# Sensorboard.net
KiCad netlist of a schematic drawn in EAGLE
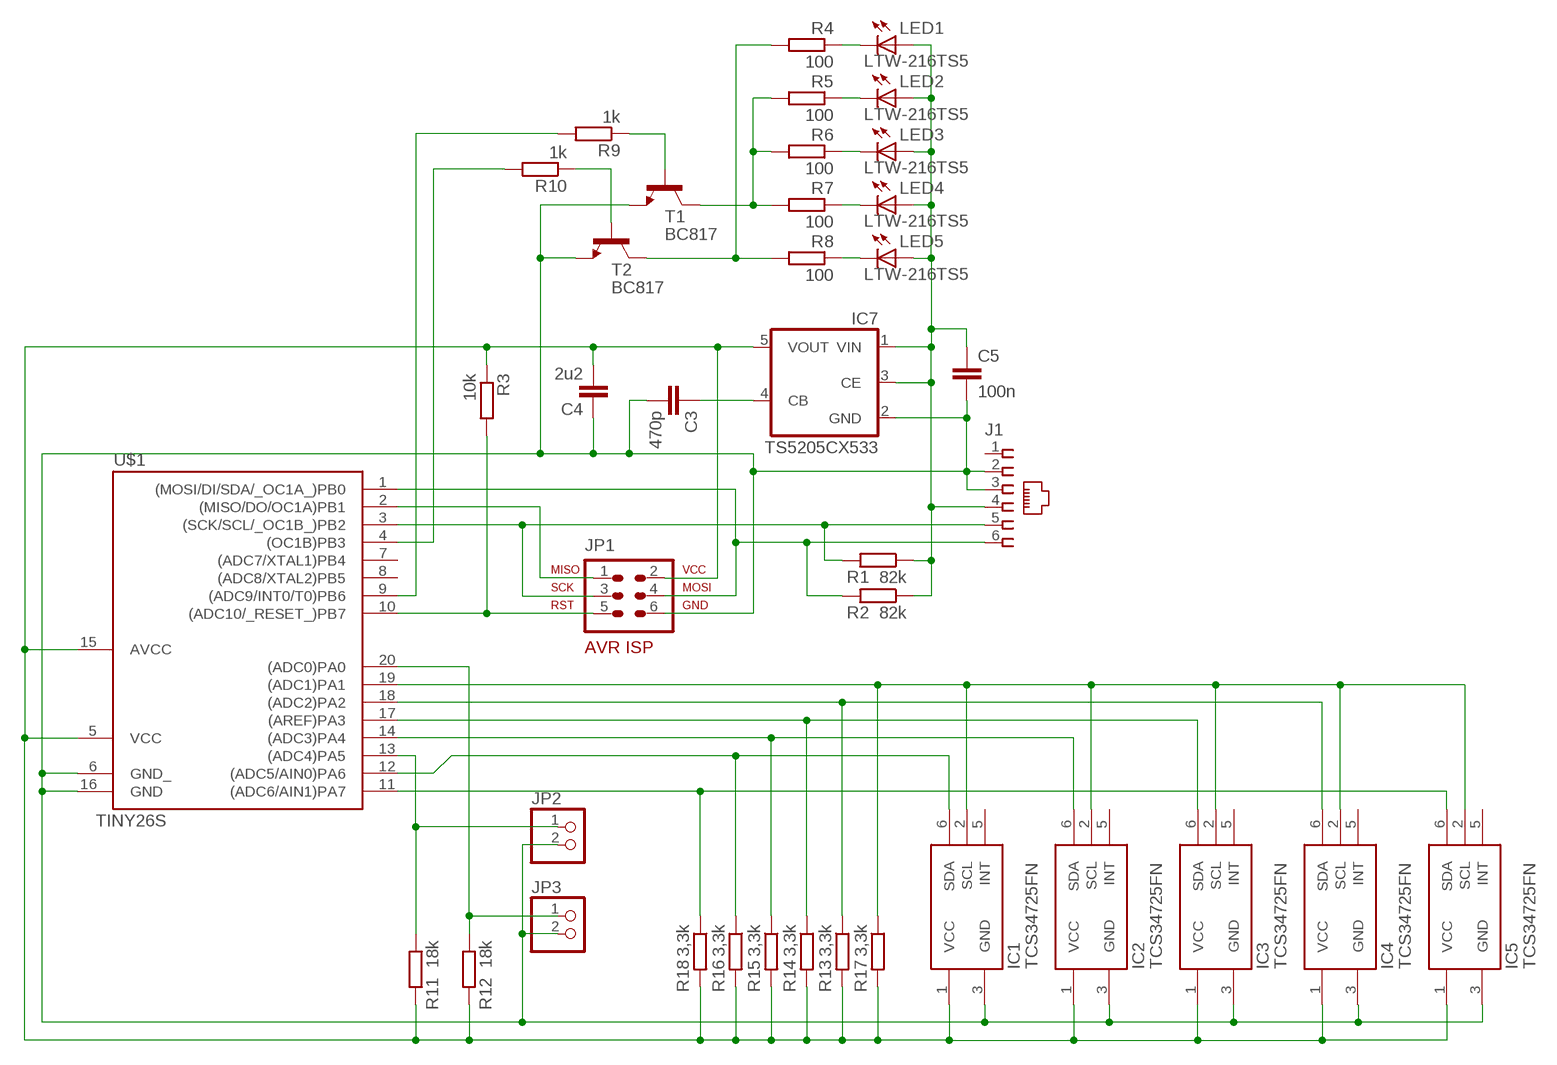
[diagram p0: schematic, sheet 1]

(export (version "E")
  (design (tool "Eeschema 10.0.6"))
  (components
    (comp (ref "C3")
      (value "470p")
      (footprint "eagle-import:C2012")
      (libsource (lib "eagle-import") (part "C-EUC2012"))
    )
    (comp (ref "C4")
      (value "2u2")
      (footprint "eagle-import:C2012")
      (libsource (lib "eagle-import") (part "C-EUC2012"))
    )
    (comp (ref "C5")
      (value "100n")
      (footprint "eagle-import:C2012")
      (libsource (lib "eagle-import") (part "C-EUC2012"))
    )
    (comp (ref "IC1")
      (value "TCS34725FN")
      (footprint "eagle-import:DFN-6")
      (libsource (lib "eagle-import") (part "TCS3472FN"))
    )
    (comp (ref "IC2")
      (value "TCS34725FN")
      (footprint "eagle-import:DFN-6")
      (libsource (lib "eagle-import") (part "TCS3472FN"))
    )
    (comp (ref "IC3")
      (value "TCS34725FN")
      (footprint "eagle-import:DFN-6")
      (libsource (lib "eagle-import") (part "TCS3472FN"))
    )
    (comp (ref "IC4")
      (value "TCS34725FN")
      (footprint "eagle-import:DFN-6")
      (libsource (lib "eagle-import") (part "TCS3472FN"))
    )
    (comp (ref "IC5")
      (value "TCS34725FN")
      (footprint "eagle-import:DFN-6")
      (libsource (lib "eagle-import") (part "TCS3472FN"))
    )
    (comp (ref "IC7")
      (value "TS5205CX533")
      (footprint "eagle-import:SOT25")
      (libsource (lib "eagle-import") (part "TS520533"))
    )
    (comp (ref "J1")
      (value "NXT")
      (footprint "eagle-import:NXT")
      (libsource (lib "eagle-import") (part "NXT"))
    )
    (comp (ref "JP1")
      (value "AVR-ISP-6VERT")
      (footprint "eagle-import:AVR-ISP-6")
      (libsource (lib "eagle-import") (part "AVR-ISP-6VERT"))
    )
    (comp (ref "JP2")
      (value "PINHD-1X2")
      (footprint "eagle-import:1X02")
      (libsource (lib "eagle-import") (part "PINHD-1X2"))
    )
    (comp (ref "JP3")
      (value "PINHD-1X2")
      (footprint "eagle-import:1X02")
      (libsource (lib "eagle-import") (part "PINHD-1X2"))
    )
    (comp (ref "LED1")
      (value "LTW-216TS5")
      (footprint "eagle-import:CHIPLED_1206")
      (libsource (lib "eagle-import") (part "LEDCHIPLED_1206"))
    )
    (comp (ref "LED2")
      (value "LTW-216TS5")
      (footprint "eagle-import:CHIPLED_1206")
      (libsource (lib "eagle-import") (part "LEDCHIPLED_1206"))
    )
    (comp (ref "LED3")
      (value "LTW-216TS5")
      (footprint "eagle-import:CHIPLED_1206")
      (libsource (lib "eagle-import") (part "LEDCHIPLED_1206"))
    )
    (comp (ref "LED4")
      (value "LTW-216TS5")
      (footprint "eagle-import:CHIPLED_1206")
      (libsource (lib "eagle-import") (part "LEDCHIPLED_1206"))
    )
    (comp (ref "LED5")
      (value "LTW-216TS5")
      (footprint "eagle-import:CHIPLED_1206")
      (libsource (lib "eagle-import") (part "LEDCHIPLED_1206"))
    )
    (comp (ref "R1")
      (value "82k")
      (footprint "eagle-import:M0805")
      (libsource (lib "eagle-import") (part "R-EU_M0805"))
    )
    (comp (ref "R2")
      (value "82k")
      (footprint "eagle-import:M0805")
      (libsource (lib "eagle-import") (part "R-EU_M0805"))
    )
    (comp (ref "R3")
      (value "10k")
      (footprint "eagle-import:M0805")
      (libsource (lib "eagle-import") (part "R-EU_M0805"))
    )
    (comp (ref "R4")
      (value "100")
      (footprint "eagle-import:M0805")
      (libsource (lib "eagle-import") (part "R-EU_M0805"))
    )
    (comp (ref "R5")
      (value "100")
      (footprint "eagle-import:M0805")
      (libsource (lib "eagle-import") (part "R-EU_M0805"))
    )
    (comp (ref "R6")
      (value "100")
      (footprint "eagle-import:M0805")
      (libsource (lib "eagle-import") (part "R-EU_M0805"))
    )
    (comp (ref "R7")
      (value "100")
      (footprint "eagle-import:M0805")
      (libsource (lib "eagle-import") (part "R-EU_M0805"))
    )
    (comp (ref "R8")
      (value "100")
      (footprint "eagle-import:M0805")
      (libsource (lib "eagle-import") (part "R-EU_M0805"))
    )
    (comp (ref "R9")
      (value "1k")
      (footprint "eagle-import:M0805")
      (libsource (lib "eagle-import") (part "R-EU_M0805"))
    )
    (comp (ref "R10")
      (value "1k")
      (footprint "eagle-import:M0805")
      (libsource (lib "eagle-import") (part "R-EU_M0805"))
    )
    (comp (ref "R11")
      (value "18k")
      (footprint "eagle-import:M0805")
      (libsource (lib "eagle-import") (part "R-EU_M0805"))
    )
    (comp (ref "R12")
      (value "18k")
      (footprint "eagle-import:M0805")
      (libsource (lib "eagle-import") (part "R-EU_M0805"))
    )
    (comp (ref "R13")
      (value "3,3k")
      (footprint "eagle-import:M0805")
      (libsource (lib "eagle-import") (part "R-EU_M0805"))
    )
    (comp (ref "R14")
      (value "3,3k")
      (footprint "eagle-import:M0805")
      (libsource (lib "eagle-import") (part "R-EU_M0805"))
    )
    (comp (ref "R15")
      (value "3,3k")
      (footprint "eagle-import:M0805")
      (libsource (lib "eagle-import") (part "R-EU_M0805"))
    )
    (comp (ref "R16")
      (value "3,3k")
      (footprint "eagle-import:M0805")
      (libsource (lib "eagle-import") (part "R-EU_M0805"))
    )
    (comp (ref "R17")
      (value "3,3k")
      (footprint "eagle-import:M0805")
      (libsource (lib "eagle-import") (part "R-EU_M0805"))
    )
    (comp (ref "R18")
      (value "3,3k")
      (footprint "eagle-import:M0805")
      (libsource (lib "eagle-import") (part "R-EU_M0805"))
    )
    (comp (ref "T1")
      (value "BC817")
      (footprint "eagle-import:SOT23")
      (libsource (lib "eagle-import") (part "BC846"))
    )
    (comp (ref "T2")
      (value "BC817")
      (footprint "eagle-import:SOT23")
      (libsource (lib "eagle-import") (part "BC846"))
    )
    (comp (ref "U$1")
      (value "TINY26S")
      (footprint "eagle-import:SO20L$")
      (libsource (lib "eagle-import") (part "TINY26S"))
    )
  )
  (nets
    (net (code "1") (name "Net-(IC1-GND)") (class "Default")
      (node (ref "C3") (pin "2") (pinfunction "2_2") (pintype "passive"))
      (node (ref "C4") (pin "1") (pinfunction "1_1") (pintype "passive"))
      (node (ref "C5") (pin "2") (pinfunction "2_2") (pintype "passive"))
      (node (ref "IC1") (pin "3") (pinfunction "GND_3") (pintype "power_in"))
      (node (ref "IC2") (pin "3") (pinfunction "GND_3") (pintype "power_in"))
      (node (ref "IC3") (pin "3") (pinfunction "GND_3") (pintype "power_in"))
      (node (ref "IC4") (pin "3") (pinfunction "GND_3") (pintype "power_in"))
      (node (ref "IC5") (pin "3") (pinfunction "GND_3") (pintype "power_in"))
      (node (ref "IC7") (pin "2") (pinfunction "GND_2") (pintype "passive"))
      (node (ref "J1") (pin "2") (pinfunction "2_2") (pintype "passive"))
      (node (ref "J1") (pin "3") (pinfunction "3_3") (pintype "passive"))
      (node (ref "JP1") (pin "6") (pinfunction "6_6") (pintype "passive"))
      (node (ref "JP2") (pin "2") (pinfunction "2_2") (pintype "passive"))
      (node (ref "JP3") (pin "2") (pinfunction "2_2") (pintype "passive"))
      (node (ref "T1") (pin "2") (pinfunction "E_2") (pintype "passive"))
      (node (ref "T2") (pin "2") (pinfunction "E_2") (pintype "passive"))
      (node (ref "U$1") (pin "16") (pinfunction "GND_16") (pintype "power_in"))
      (node (ref "U$1") (pin "6") (pinfunction "GND__6") (pintype "power_in"))
    )
    (net (code "2") (name "Net-(IC1-SCL)") (class "Default")
      (node (ref "IC1") (pin "2") (pinfunction "SCL_2") (pintype "bidirectional"))
      (node (ref "IC2") (pin "2") (pinfunction "SCL_2") (pintype "bidirectional"))
      (node (ref "IC3") (pin "2") (pinfunction "SCL_2") (pintype "bidirectional"))
      (node (ref "IC4") (pin "2") (pinfunction "SCL_2") (pintype "bidirectional"))
      (node (ref "IC5") (pin "2") (pinfunction "SCL_2") (pintype "bidirectional"))
      (node (ref "R17") (pin "1") (pinfunction "1_1") (pintype "passive"))
      (node (ref "U$1") (pin "19") (pinfunction "(ADC1)PA1_19") (pintype "bidirectional"))
    )
    (net (code "3") (name "Net-(IC1-SDA)") (class "Default")
      (node (ref "IC1") (pin "6") (pinfunction "SDA_6") (pintype "bidirectional"))
      (node (ref "R16") (pin "1") (pinfunction "1_1") (pintype "passive"))
      (node (ref "U$1") (pin "12") (pinfunction "(ADC5/AIN0)PA6_12") (pintype "bidirectional"))
    )
    (net (code "4") (name "Net-(IC1-VCC)") (class "Default")
      (node (ref "C4") (pin "2") (pinfunction "2_2") (pintype "passive"))
      (node (ref "IC1") (pin "1") (pinfunction "VCC_1") (pintype "power_in"))
      (node (ref "IC2") (pin "1") (pinfunction "VCC_1") (pintype "power_in"))
      (node (ref "IC3") (pin "1") (pinfunction "VCC_1") (pintype "power_in"))
      (node (ref "IC4") (pin "1") (pinfunction "VCC_1") (pintype "power_in"))
      (node (ref "IC5") (pin "1") (pinfunction "VCC_1") (pintype "power_in"))
      (node (ref "IC7") (pin "5") (pinfunction "VOUT_5") (pintype "passive"))
      (node (ref "JP1") (pin "2") (pinfunction "2_2") (pintype "passive"))
      (node (ref "R11") (pin "2") (pinfunction "2_2") (pintype "passive"))
      (node (ref "R12") (pin "2") (pinfunction "2_2") (pintype "passive"))
      (node (ref "R13") (pin "2") (pinfunction "2_2") (pintype "passive"))
      (node (ref "R14") (pin "2") (pinfunction "2_2") (pintype "passive"))
      (node (ref "R15") (pin "2") (pinfunction "2_2") (pintype "passive"))
      (node (ref "R16") (pin "2") (pinfunction "2_2") (pintype "passive"))
      (node (ref "R17") (pin "2") (pinfunction "2_2") (pintype "passive"))
      (node (ref "R18") (pin "2") (pinfunction "2_2") (pintype "passive"))
      (node (ref "R3") (pin "1") (pinfunction "1_1") (pintype "passive"))
      (node (ref "U$1") (pin "15") (pinfunction "AVCC_15") (pintype "power_in"))
      (node (ref "U$1") (pin "5") (pinfunction "VCC_5") (pintype "power_in"))
    )
    (net (code "5") (name "Net-(IC2-SDA)") (class "Default")
      (node (ref "IC2") (pin "6") (pinfunction "SDA_6") (pintype "bidirectional"))
      (node (ref "R15") (pin "1") (pinfunction "1_1") (pintype "passive"))
      (node (ref "U$1") (pin "14") (pinfunction "(ADC3)PA4_14") (pintype "bidirectional"))
    )
    (net (code "6") (name "Net-(IC3-SDA)") (class "Default")
      (node (ref "IC3") (pin "6") (pinfunction "SDA_6") (pintype "bidirectional"))
      (node (ref "R14") (pin "1") (pinfunction "1_1") (pintype "passive"))
      (node (ref "U$1") (pin "17") (pinfunction "(AREF)PA3_17") (pintype "bidirectional"))
    )
    (net (code "7") (name "Net-(IC4-SDA)") (class "Default")
      (node (ref "IC4") (pin "6") (pinfunction "SDA_6") (pintype "bidirectional"))
      (node (ref "R13") (pin "1") (pinfunction "1_1") (pintype "passive"))
      (node (ref "U$1") (pin "18") (pinfunction "(ADC2)PA2_18") (pintype "bidirectional"))
    )
    (net (code "8") (name "Net-(IC5-SDA)") (class "Default")
      (node (ref "IC5") (pin "6") (pinfunction "SDA_6") (pintype "bidirectional"))
      (node (ref "R18") (pin "1") (pinfunction "1_1") (pintype "passive"))
      (node (ref "U$1") (pin "11") (pinfunction "(ADC6/AIN1)PA7_11") (pintype "bidirectional"))
    )
    (net (code "9") (name "Net-(IC7-CB)") (class "Default")
      (node (ref "C3") (pin "1") (pinfunction "1_1") (pintype "passive"))
      (node (ref "IC7") (pin "4") (pinfunction "CB_4") (pintype "input"))
    )
    (net (code "10") (name "Net-(IC7-CE)") (class "Default")
      (node (ref "C5") (pin "1") (pinfunction "1_1") (pintype "passive"))
      (node (ref "IC7") (pin "1") (pinfunction "VIN_1") (pintype "input"))
      (node (ref "IC7") (pin "3") (pinfunction "CE_3") (pintype "input"))
      (node (ref "J1") (pin "4") (pinfunction "4_4") (pintype "passive"))
      (node (ref "LED1") (pin "A") (pinfunction "A_A") (pintype "passive"))
      (node (ref "LED2") (pin "A") (pinfunction "A_A") (pintype "passive"))
      (node (ref "LED3") (pin "A") (pinfunction "A_A") (pintype "passive"))
      (node (ref "LED4") (pin "A") (pinfunction "A_A") (pintype "passive"))
      (node (ref "LED5") (pin "A") (pinfunction "A_A") (pintype "passive"))
      (node (ref "R1") (pin "1") (pinfunction "1_1") (pintype "passive"))
      (node (ref "R2") (pin "1") (pinfunction "1_1") (pintype "passive"))
    )
    (net (code "11") (name "Net-(LED1-PadC)") (class "Default")
      (node (ref "LED1") (pin "C") (pinfunction "C_C") (pintype "passive"))
      (node (ref "R4") (pin "1") (pinfunction "1_1") (pintype "passive"))
    )
    (net (code "12") (name "Net-(LED2-PadC)") (class "Default")
      (node (ref "LED2") (pin "C") (pinfunction "C_C") (pintype "passive"))
      (node (ref "R5") (pin "1") (pinfunction "1_1") (pintype "passive"))
    )
    (net (code "13") (name "Net-(LED3-PadC)") (class "Default")
      (node (ref "LED3") (pin "C") (pinfunction "C_C") (pintype "passive"))
      (node (ref "R6") (pin "1") (pinfunction "1_1") (pintype "passive"))
    )
    (net (code "14") (name "Net-(LED4-PadC)") (class "Default")
      (node (ref "LED4") (pin "C") (pinfunction "C_C") (pintype "passive"))
      (node (ref "R7") (pin "1") (pinfunction "1_1") (pintype "passive"))
    )
    (net (code "15") (name "Net-(LED5-PadC)") (class "Default")
      (node (ref "LED5") (pin "C") (pinfunction "C_C") (pintype "passive"))
      (node (ref "R8") (pin "1") (pinfunction "1_1") (pintype "passive"))
    )
    (net (code "16") (name "Net-(T1-B)") (class "Default")
      (node (ref "R9") (pin "1") (pinfunction "1_1") (pintype "passive"))
      (node (ref "T1") (pin "1") (pinfunction "B_1") (pintype "passive"))
    )
    (net (code "17") (name "Net-(T1-C)") (class "Default")
      (node (ref "R5") (pin "2") (pinfunction "2_2") (pintype "passive"))
      (node (ref "R6") (pin "2") (pinfunction "2_2") (pintype "passive"))
      (node (ref "R7") (pin "2") (pinfunction "2_2") (pintype "passive"))
      (node (ref "T1") (pin "3") (pinfunction "C_3") (pintype "passive"))
    )
    (net (code "18") (name "Net-(T2-B)") (class "Default")
      (node (ref "R10") (pin "1") (pinfunction "1_1") (pintype "passive"))
      (node (ref "T2") (pin "1") (pinfunction "B_1") (pintype "passive"))
    )
    (net (code "19") (name "Net-(T2-C)") (class "Default")
      (node (ref "R4") (pin "2") (pinfunction "2_2") (pintype "passive"))
      (node (ref "R8") (pin "2") (pinfunction "2_2") (pintype "passive"))
      (node (ref "T2") (pin "3") (pinfunction "C_3") (pintype "passive"))
    )
    (net (code "20") (name "Net-(U$1-(ADC0)PA0)") (class "Default")
      (node (ref "JP3") (pin "1") (pinfunction "1_1") (pintype "passive"))
      (node (ref "R12") (pin "1") (pinfunction "1_1") (pintype "passive"))
      (node (ref "U$1") (pin "20") (pinfunction "(ADC0)PA0_20") (pintype "bidirectional"))
    )
    (net (code "21") (name "Net-(U$1-(ADC4)PA5)") (class "Default")
      (node (ref "JP2") (pin "1") (pinfunction "1_1") (pintype "passive"))
      (node (ref "R11") (pin "1") (pinfunction "1_1") (pintype "passive"))
      (node (ref "U$1") (pin "13") (pinfunction "(ADC4)PA5_13") (pintype "bidirectional"))
    )
    (net (code "22") (name "Net-(U$1-(ADC9{slash}INT0{slash}T0)PB6)") (class "Default")
      (node (ref "R9") (pin "2") (pinfunction "2_2") (pintype "passive"))
      (node (ref "U$1") (pin "9") (pinfunction "(ADC9/INT0/T0)PB6_9") (pintype "bidirectional"))
    )
    (net (code "23") (name "Net-(U$1-(ADC10{slash}_RESET_)PB7)") (class "Default")
      (node (ref "JP1") (pin "5") (pinfunction "5_5") (pintype "passive"))
      (node (ref "R3") (pin "2") (pinfunction "2_2") (pintype "passive"))
      (node (ref "U$1") (pin "10") (pinfunction "(ADC10/_RESET_)PB7_10") (pintype "bidirectional"))
    )
    (net (code "24") (name "Net-(U$1-(MISO{slash}DO{slash}OC1A)PB1)") (class "Default")
      (node (ref "JP1") (pin "1") (pinfunction "1_1") (pintype "passive"))
      (node (ref "U$1") (pin "2") (pinfunction "(MISO/DO/OC1A)PB1_2") (pintype "bidirectional"))
    )
    (net (code "25") (name "Net-(U$1-(MOSI{slash}DI{slash}SDA{slash}_OC1A_)PB0)") (class "Default")
      (node (ref "J1") (pin "6") (pinfunction "6_6") (pintype "passive"))
      (node (ref "JP1") (pin "4") (pinfunction "4_4") (pintype "passive"))
      (node (ref "R2") (pin "2") (pinfunction "2_2") (pintype "passive"))
      (node (ref "U$1") (pin "1") (pinfunction "(MOSI/DI/SDA/_OC1A_)PB0_1") (pintype "bidirectional"))
    )
    (net (code "26") (name "Net-(U$1-(OC1B)PB3)") (class "Default")
      (node (ref "R10") (pin "2") (pinfunction "2_2") (pintype "passive"))
      (node (ref "U$1") (pin "4") (pinfunction "(OC1B)PB3_4") (pintype "bidirectional"))
    )
    (net (code "27") (name "Net-(U$1-(SCK{slash}SCL{slash}_OC1B_)PB2)") (class "Default")
      (node (ref "J1") (pin "5") (pinfunction "5_5") (pintype "passive"))
      (node (ref "JP1") (pin "3") (pinfunction "3_3") (pintype "passive"))
      (node (ref "R1") (pin "2") (pinfunction "2_2") (pintype "passive"))
      (node (ref "U$1") (pin "3") (pinfunction "(SCK/SCL/_OC1B_)PB2_3") (pintype "bidirectional"))
    )
    (net (code "28") (name "unconnected-(IC1-INT-Pad5)") (class "Default")
      (node (ref "IC1") (pin "5") (pinfunction "INT_5") (pintype "output"))
    )
    (net (code "29") (name "unconnected-(IC2-INT-Pad5)") (class "Default")
      (node (ref "IC2") (pin "5") (pinfunction "INT_5") (pintype "output"))
    )
    (net (code "30") (name "unconnected-(IC3-INT-Pad5)") (class "Default")
      (node (ref "IC3") (pin "5") (pinfunction "INT_5") (pintype "output"))
    )
    (net (code "31") (name "unconnected-(IC4-INT-Pad5)") (class "Default")
      (node (ref "IC4") (pin "5") (pinfunction "INT_5") (pintype "output"))
    )
    (net (code "32") (name "unconnected-(IC5-INT-Pad5)") (class "Default")
      (node (ref "IC5") (pin "5") (pinfunction "INT_5") (pintype "output"))
    )
    (net (code "33") (name "unconnected-(J1-Pad1)") (class "Default")
      (node (ref "J1") (pin "1") (pinfunction "1_1") (pintype "passive"))
    )
    (net (code "34") (name "unconnected-(U$1-(ADC7{slash}XTAL1)PB4-Pad7)") (class "Default")
      (node (ref "U$1") (pin "7") (pinfunction "(ADC7/XTAL1)PB4_7") (pintype "bidirectional"))
    )
    (net (code "35") (name "unconnected-(U$1-(ADC8{slash}XTAL2)PB5-Pad8)") (class "Default")
      (node (ref "U$1") (pin "8") (pinfunction "(ADC8/XTAL2)PB5_8") (pintype "bidirectional"))
    )
  )
)
